# MotorActuatorJack.net
KiCad netlist of a schematic drawn in EAGLE
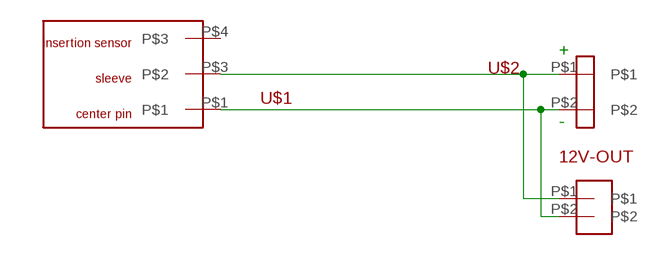
[diagram p0: schematic, sheet 1]

(export (version "E")
  (design (tool "Eeschema 10.0.6"))
  (components
    (comp (ref "12V-OUT")
      (value "1X2HEADER_ROBBIE")
      (footprint "eagle-import:1X2HEADER_ROBBIE")
      (libsource (lib "eagle-import") (part "1X2HEADER_ROBBIE"))
    )
    (comp (ref "U$1")
      (value "PJ-014CH-SMT")
      (footprint "eagle-import:PJ-014CH-SMT")
      (libsource (lib "eagle-import") (part "PJ-014CH-SMT"))
    )
    (comp (ref "U$2")
      (value "3.5MM_2PIN_SCREWTERMINAL_SPARKFUN")
      (footprint "eagle-import:1X02_3.5_SCREWTERM")
      (libsource (lib "eagle-import") (part "3.5MM_2PIN_SCREWTERMINAL_SPARKFUN"))
    )
  )
  (nets
    (net (code "1") (name "Net-(12V-OUT-PadP$2)") (class "Default")
      (node (ref "12V-OUT") (pin "P$2") (pinfunction "P$2_P$2") (pintype "bidirectional"))
      (node (ref "U$1") (pin "P$1") (pinfunction "P$1_P$1") (pintype "bidirectional"))
      (node (ref "U$2") (pin "P$2") (pinfunction "P$2_P$2") (pintype "bidirectional"))
    )
    (net (code "2") (name "Net-(U$1-P$2)") (class "Default")
      (node (ref "12V-OUT") (pin "P$1") (pinfunction "P$1_P$1") (pintype "bidirectional"))
      (node (ref "U$1") (pin "P$3") (pinfunction "P$2_P$3") (pintype "bidirectional"))
      (node (ref "U$2") (pin "P$1") (pinfunction "P$1_P$1") (pintype "bidirectional"))
    )
    (net (code "3") (name "unconnected-(U$1-P$3-PadP$4)") (class "Default")
      (node (ref "U$1") (pin "P$4") (pinfunction "P$3_P$4") (pintype "bidirectional"))
    )
  )
)
